# AMP.net
KiCad netlist of a schematic drawn in Altium Designer
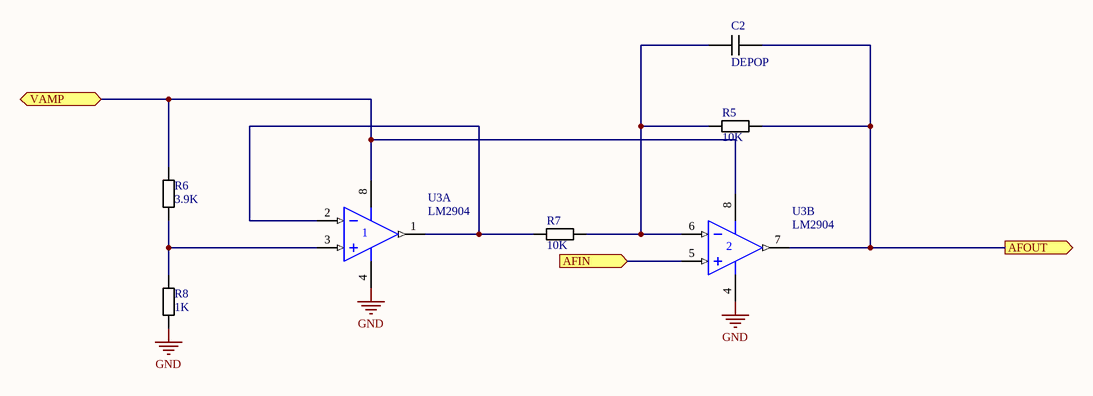
[diagram p0: AMP.SchDoc]

(export (version "E")
  (design (tool "Eeschema 10.0.6"))
  (components
    (comp (ref "C2")
      (value "DEPOP")
      (footprint "0805 Cap")
      (description "0805 MLCC - NP0, 5%")
      (fields (field (name "Comment") "0805 Cap"))
      (libsource (lib "Schlib1") (part "0805 MLCC - NP0, 5%"))
    )
    (comp (ref "R5")
      (value "10K")
      (footprint "0805 Resistor")
      (description "0805 Thick Film Resistor 1%")
      (fields (field (name "Comment") "0805 Resistor"))
      (libsource (lib "Schlib1") (part "0805 Thick Film Resistor 1%"))
    )
    (comp (ref "R6")
      (value "3.9K")
      (footprint "0805 Resistor")
      (description "0805 Thick Film Resistor 1%")
      (fields (field (name "Comment") "0805 Resistor"))
      (libsource (lib "") (part "0805 Thick Film Resistor 1%_2"))
    )
    (comp (ref "R7")
      (value "10K")
      (footprint "0805 Resistor")
      (description "0805 Thick Film Resistor 1%")
      (fields (field (name "Comment") "0805 Resistor"))
      (libsource (lib "Schlib1") (part "0805 Thick Film Resistor 1%"))
    )
    (comp (ref "R8")
      (value "1K")
      (footprint "0805 Resistor")
      (description "0805 Thick Film Resistor 1%")
      (fields (field (name "Comment") "0805 Resistor"))
      (libsource (lib "") (part "0805 Thick Film Resistor 1%_1"))
    )
    (comp (ref "U3")
      (value "LM2904")
      (footprint "SOIC8 - LT1120A")
      (description "Dual Operational Amplifier")
      (libsource (lib "Schlib1") (part "LM2904"))
    )
  )
  (nets
    (net (code "1") (name "/AFIN") (class "Default")
      (node (ref "U3") (pin "5") (pinfunction "IN+_5") (pintype "input"))
    )
    (net (code "2") (name "/AFOUT") (class "Default")
      (node (ref "C2") (pin "2") (pinfunction "2_2") (pintype "passive"))
      (node (ref "R5") (pin "2") (pinfunction "2_2") (pintype "passive"))
      (node (ref "U3") (pin "7") (pinfunction "OUT_7") (pintype "output"))
    )
    (net (code "3") (name "/VAMP") (class "Default")
      (node (ref "R6") (pin "1") (pinfunction "1_1") (pintype "passive"))
      (node (ref "U3") (pin "8") (pinfunction "V+_8") (pintype "power_in"))
    )
    (net (code "4") (name "GND") (class "Default")
      (node (ref "R8") (pin "1") (pinfunction "1_1") (pintype "passive"))
      (node (ref "U3") (pin "4") (pinfunction "V+_4") (pintype "power_in"))
    )
    (net (code "5") (name "Net-(U3A-IN+)") (class "Default")
      (node (ref "R6") (pin "2") (pinfunction "2_2") (pintype "passive"))
      (node (ref "R8") (pin "2") (pinfunction "2_2") (pintype "passive"))
      (node (ref "U3") (pin "3") (pinfunction "IN+_3") (pintype "input"))
    )
    (net (code "6") (name "Net-(U3A-IN-)") (class "Default")
      (node (ref "R7") (pin "1") (pinfunction "1_1") (pintype "passive"))
      (node (ref "U3") (pin "1") (pinfunction "OUT_1") (pintype "output"))
      (node (ref "U3") (pin "2") (pinfunction "IN-_2") (pintype "input"))
    )
    (net (code "7") (name "Net-(U3B-IN-)") (class "Default")
      (node (ref "C2") (pin "1") (pinfunction "1_1") (pintype "passive"))
      (node (ref "R5") (pin "1") (pinfunction "1_1") (pintype "passive"))
      (node (ref "R7") (pin "2") (pinfunction "2_2") (pintype "passive"))
      (node (ref "U3") (pin "6") (pinfunction "IN-_6") (pintype "input"))
    )
  )
)
